# design.net
KiCad netlist of a schematic drawn in EasyEDA Pro
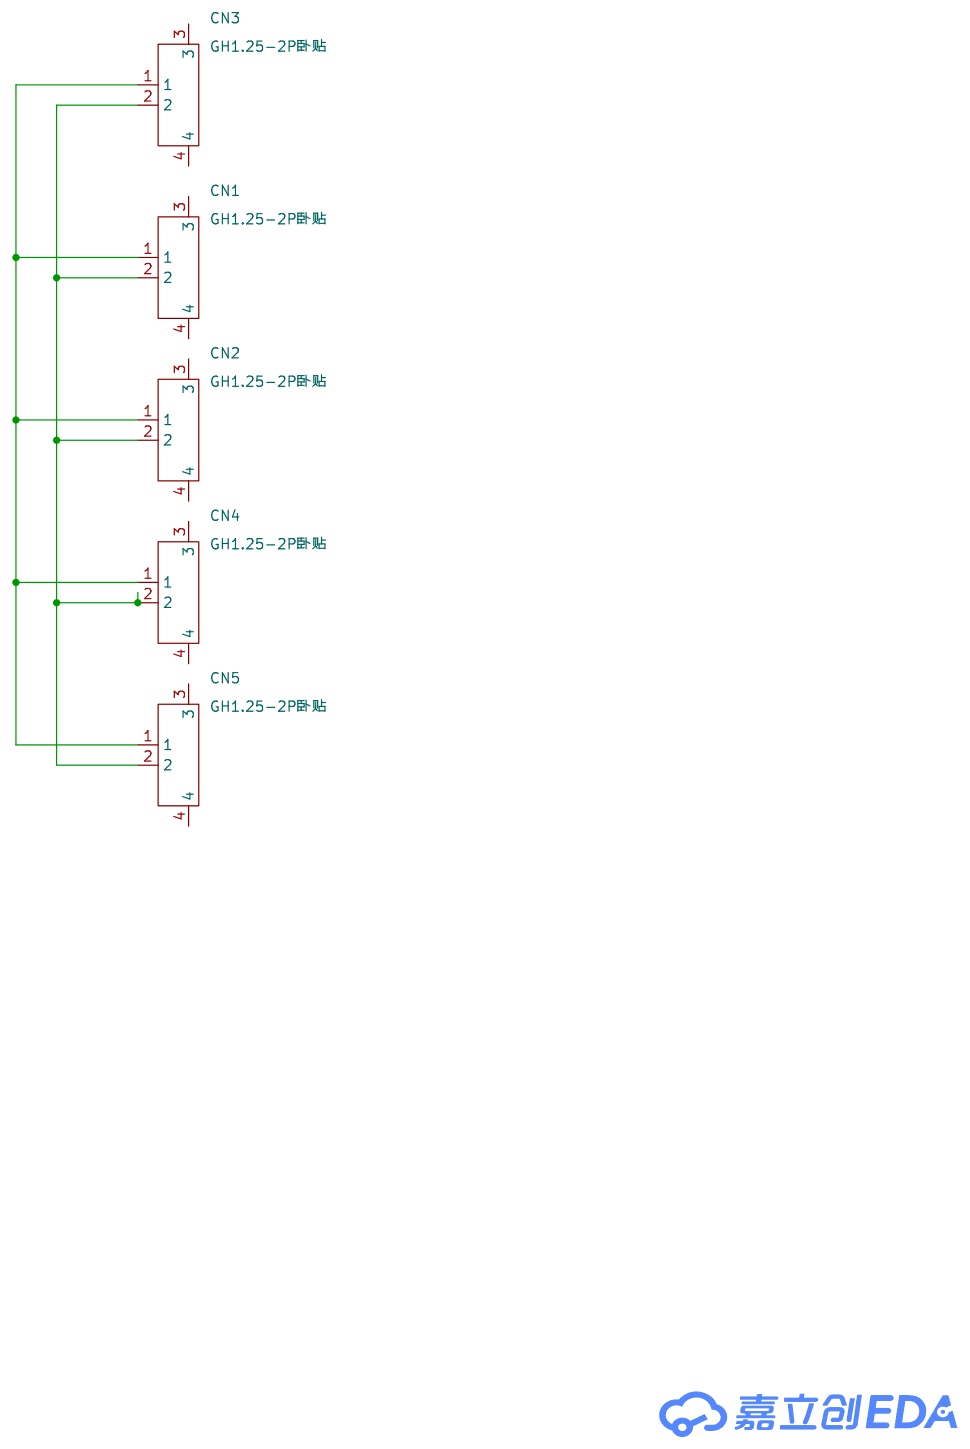
[diagram p0: schematic sheet]

(export (version "E")
  (design (tool "Eeschema 10.0.6"))
  (components
    (comp (ref "CN1")
      (value "GH1.25-2P卧贴")
      (footprint "easyedapro:CONN-SMD_2P-P1.25_X1251WRS-02HF-LPSW")
      (libsource (lib "easyedapro") (part "GH1.25-2P卧贴_C9900015099"))
    )
    (comp (ref "CN2")
      (value "GH1.25-2P卧贴")
      (footprint "easyedapro:CONN-SMD_2P-P1.25_X1251WRS-02HF-LPSW")
      (libsource (lib "easyedapro") (part "GH1.25-2P卧贴_C9900015099"))
    )
    (comp (ref "CN3")
      (value "GH1.25-2P卧贴")
      (footprint "easyedapro:CONN-SMD_2P-P1.25_X1251WRS-02HF-LPSW")
      (libsource (lib "easyedapro") (part "GH1.25-2P卧贴_C9900015099"))
    )
    (comp (ref "CN4")
      (value "GH1.25-2P卧贴")
      (footprint "easyedapro:CONN-SMD_2P-P1.25_X1251WRS-02HF-LPSW")
      (libsource (lib "easyedapro") (part "GH1.25-2P卧贴_C9900015099"))
    )
    (comp (ref "CN5")
      (value "GH1.25-2P卧贴")
      (footprint "easyedapro:CONN-SMD_2P-P1.25_X1251WRS-02HF-LPSW")
      (libsource (lib "easyedapro") (part "GH1.25-2P卧贴_C9900015099"))
    )
  )
  (nets
    (net (code "1") (name "Net-(CN1-Pad1)") (class "Default")
      (node (ref "CN1") (pin "1") (pinfunction "1_1") (pintype "unspecified"))
      (node (ref "CN2") (pin "1") (pinfunction "1_1") (pintype "unspecified"))
      (node (ref "CN3") (pin "1") (pinfunction "1_1") (pintype "unspecified"))
      (node (ref "CN4") (pin "1") (pinfunction "1_1") (pintype "unspecified"))
      (node (ref "CN5") (pin "1") (pinfunction "1_1") (pintype "unspecified"))
    )
    (net (code "2") (name "Net-(CN1-Pad2)") (class "Default")
      (node (ref "CN1") (pin "2") (pinfunction "2_2") (pintype "unspecified"))
      (node (ref "CN2") (pin "2") (pinfunction "2_2") (pintype "unspecified"))
      (node (ref "CN3") (pin "2") (pinfunction "2_2") (pintype "unspecified"))
      (node (ref "CN4") (pin "2") (pinfunction "2_2") (pintype "unspecified"))
      (node (ref "CN5") (pin "2") (pinfunction "2_2") (pintype "unspecified"))
    )
    (net (code "3") (name "unconnected-(CN1-Pad3)") (class "Default")
      (node (ref "CN1") (pin "3") (pinfunction "3_3") (pintype "unspecified"))
    )
    (net (code "4") (name "unconnected-(CN1-Pad4)") (class "Default")
      (node (ref "CN1") (pin "4") (pinfunction "4_4") (pintype "unspecified"))
    )
    (net (code "5") (name "unconnected-(CN2-Pad3)") (class "Default")
      (node (ref "CN2") (pin "3") (pinfunction "3_3") (pintype "unspecified"))
    )
    (net (code "6") (name "unconnected-(CN2-Pad4)") (class "Default")
      (node (ref "CN2") (pin "4") (pinfunction "4_4") (pintype "unspecified"))
    )
    (net (code "7") (name "unconnected-(CN3-Pad3)") (class "Default")
      (node (ref "CN3") (pin "3") (pinfunction "3_3") (pintype "unspecified"))
    )
    (net (code "8") (name "unconnected-(CN3-Pad4)") (class "Default")
      (node (ref "CN3") (pin "4") (pinfunction "4_4") (pintype "unspecified"))
    )
    (net (code "9") (name "unconnected-(CN4-Pad3)") (class "Default")
      (node (ref "CN4") (pin "3") (pinfunction "3_3") (pintype "unspecified"))
    )
    (net (code "10") (name "unconnected-(CN4-Pad4)") (class "Default")
      (node (ref "CN4") (pin "4") (pinfunction "4_4") (pintype "unspecified"))
    )
    (net (code "11") (name "unconnected-(CN5-Pad3)") (class "Default")
      (node (ref "CN5") (pin "3") (pinfunction "3_3") (pintype "unspecified"))
    )
    (net (code "12") (name "unconnected-(CN5-Pad4)") (class "Default")
      (node (ref "CN5") (pin "4") (pinfunction "4_4") (pintype "unspecified"))
    )
  )
)
